# geneva-interface.net
KiCad netlist of a schematic drawn in Altium Designer
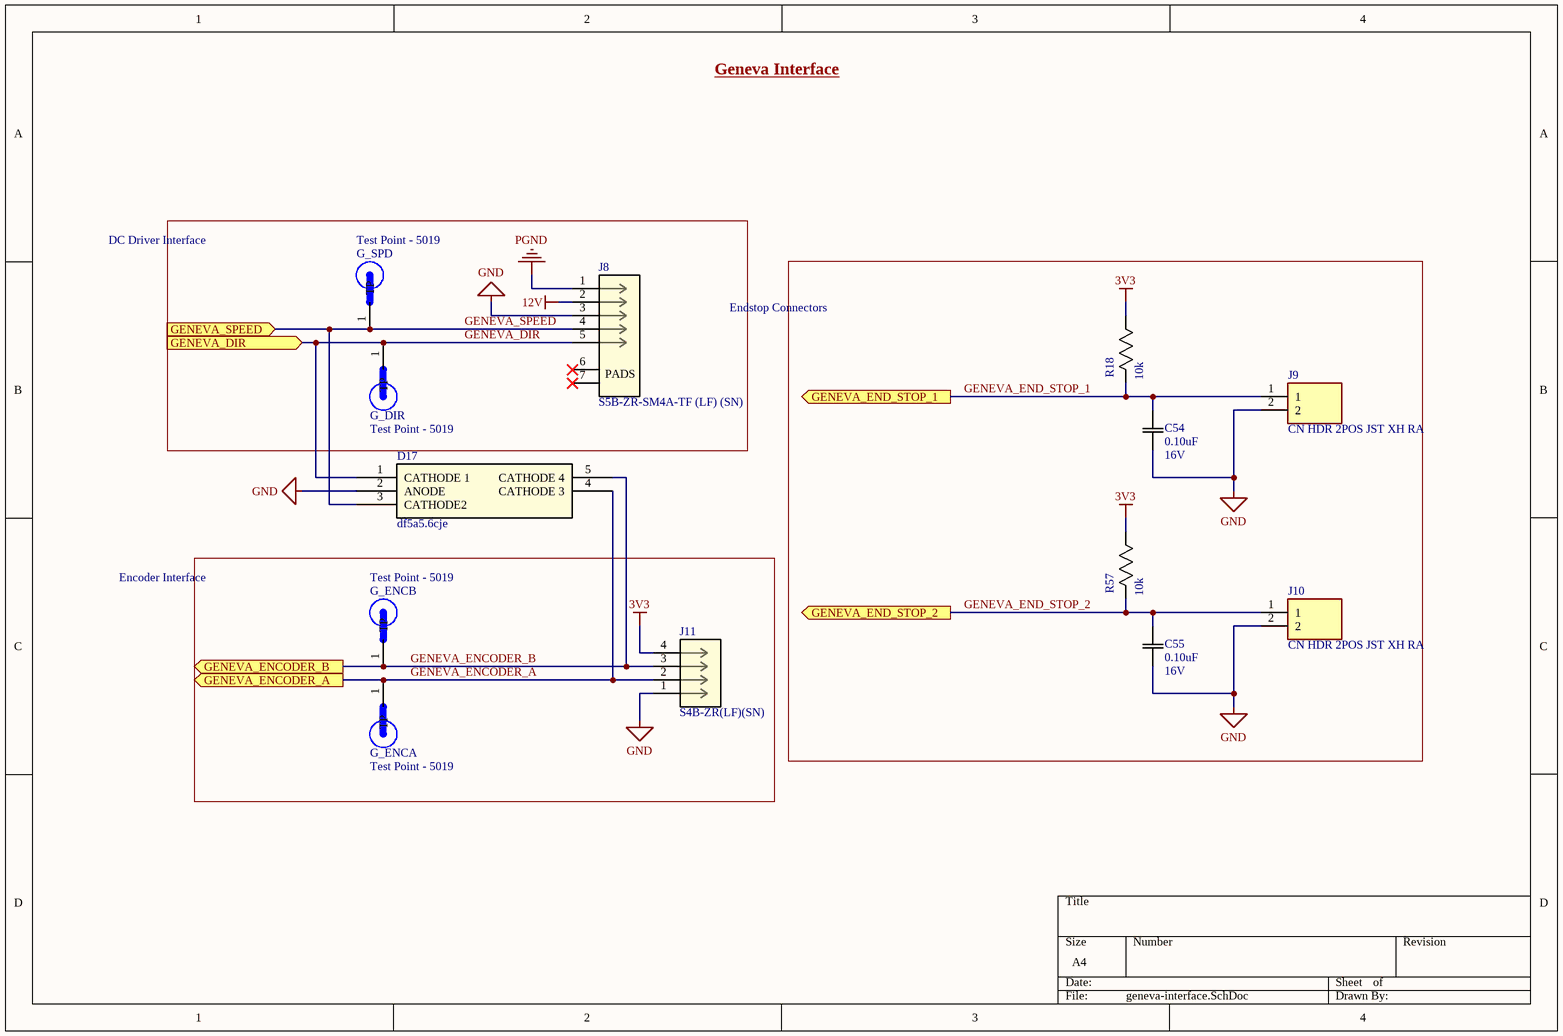
[diagram p0: geneva-interface.SchDoc]

(export (version "E")
  (design (tool "Eeschema 10.0.6"))
  (components
    (comp (ref "C54")
      (value "0.10uF")
      (footprint "0603")
      (description "CAP CER 0.10UF 16V X5R 0603")
      (fields
        (field (name "TOLERANCE") "10%")
        (field (name "RATING") "16V")
        (field (name "PART NUMBER") "CAP 0.10uF 16V")
      )
      (libsource (lib "capacitor_library") (part "CAP 0.10uF 16V"))
    )
    (comp (ref "C55")
      (value "0.10uF")
      (footprint "0603")
      (description "CAP CER 0.10UF 16V X5R 0603")
      (fields
        (field (name "TOLERANCE") "10%")
        (field (name "RATING") "16V")
        (field (name "PART NUMBER") "CAP 0.10uF 16V")
      )
      (libsource (lib "capacitor_library") (part "CAP 0.10uF 16V"))
    )
    (comp (ref "D17")
      (value "df5a5.6cje")
      (footprint "ESV_TOS-L")
      (description "- Clamp - Ipp Tvs Diode Surface Mount ESV 4 Channel")
      (fields
        (field (name "MANUFACTURER_PART_NUMBER") "df5a5.6cje(te85l")
        (field (name "PART NUMBER") "DIODE TVS 3.5 VWM 4 Channel")
        (field (name "COPYRIGHT") "Copyright (C) 2021 Ultra Librarian. All rights reserved.")
      )
      (libsource (lib "Diode_Library") (part "DIODE TVS 3.5 VWM 4 Channel"))
    )
    (comp (ref "G_DIR")
      (value "Test Point - 5019")
      (footprint "TP380X203")
      (description "PC Test Point, Miniature Phosphor Bronze, Silver Plating Surface Mount Mounting Type")
      (fields (field (name "MP") "5019") (field (name "MF") "Keystone Electronics"))
      (libsource (lib "IC_Library") (part "Test Point - 5019"))
    )
    (comp (ref "G_ENCA")
      (value "Test Point - 5019")
      (footprint "TP380X203")
      (description "PC Test Point, Miniature Phosphor Bronze, Silver Plating Surface Mount Mounting Type")
      (fields (field (name "MP") "5019") (field (name "MF") "Keystone Electronics"))
      (libsource (lib "IC_Library") (part "Test Point - 5019"))
    )
    (comp (ref "G_ENCB")
      (value "Test Point - 5019")
      (footprint "TP380X203")
      (description "PC Test Point, Miniature Phosphor Bronze, Silver Plating Surface Mount Mounting Type")
      (fields (field (name "MP") "5019") (field (name "MF") "Keystone Electronics"))
      (libsource (lib "IC_Library") (part "Test Point - 5019"))
    )
    (comp (ref "G_SPD")
      (value "Test Point - 5019")
      (footprint "TP380X203")
      (description "PC Test Point, Miniature Phosphor Bronze, Silver Plating Surface Mount Mounting Type")
      (fields (field (name "MP") "5019") (field (name "MF") "Keystone Electronics"))
      (libsource (lib "IC_Library") (part "Test Point - 5019"))
    )
    (comp (ref "J8")
      (value "S5B-ZR-SM4A-TF (LF) (SN)")
      (footprint "JST_S5B-ZR-SM4A-TF")
      (description "Connector Header Surface Mount, Right Angle 5 position 0.059\" (1.50mm)")
      (fields (field (name "PART NUMBER") "CN 5POS JST ZR RA"))
      (libsource (lib "Connector_Library") (part "CN 5POS JST ZR RA"))
    )
    (comp (ref "J9")
      (value "CN HDR 2POS JST XH RA")
      (footprint "JST_S2B-XH-A(LF)(SN)")
      (description "Connector Header Through Hole 2 position right angle 0.098 _2.50mm_\r\nJST XH")
      (fields (field (name "MP") "B2B-XH-A_LF__SN_") (field (name "MF") "JST Sales"))
      (libsource (lib "Connector_Library") (part "CN HDR 2POS JST XH RA"))
    )
    (comp (ref "J10")
      (value "CN HDR 2POS JST XH RA")
      (footprint "JST_S2B-XH-A(LF)(SN)")
      (description "Connector Header Through Hole 2 position right angle 0.098 _2.50mm_\r\nJST XH")
      (fields (field (name "MP") "B2B-XH-A_LF__SN_") (field (name "MF") "JST Sales"))
      (libsource (lib "Connector_Library") (part "CN HDR 2POS JST XH RA"))
    )
    (comp (ref "J11")
      (value "S4B-ZR(LF)(SN)")
      (footprint "CN S4B-ZR(LF)(SN)_JST")
      (description "Connector Header Through Hole, Right Angle 4 position 0.059\" (1.50mm)")
      (fields
        (field (name "PART NUMBER") "CN HDR 4POS JST ZR")
        (field (name "COPYRIGHT") "Copyright (C) 2021 Ultra Librarian. All rights reserved.")
      )
      (libsource (lib "Connector_Library") (part "CN HDR 4POS JST ZR"))
    )
    (comp (ref "R18")
      (value "10k")
      (footprint "0603")
      (description "RES SMD 10K OHM 5% 1/8W 0603")
      (fields (field (name "TOLERANCE") "5%") (field (name "PART NUMBER") "RES 10k 1/8W - 5%"))
      (libsource (lib "Resistor_Library") (part "RES 10k 1/8W 5%"))
    )
    (comp (ref "R57")
      (value "10k")
      (footprint "0603")
      (description "RES SMD 10K OHM 5% 1/8W 0603")
      (fields (field (name "TOLERANCE") "5%") (field (name "PART NUMBER") "RES 10k 1/8W - 5%"))
      (libsource (lib "Resistor_Library") (part "RES 10k 1/8W 5%"))
    )
  )
  (nets
    (net (code "1") (name "/GENEVA_DIR") (class "Default")
      (node (ref "D17") (pin "1") (pinfunction "CATHODE_1_1") (pintype "passive"))
      (node (ref "G_DIR") (pin "1") (pinfunction "TP_1") (pintype "passive"))
      (node (ref "J8") (pin "5") (pinfunction "5_5") (pintype "passive"))
    )
    (net (code "2") (name "/GENEVA_ENCODER_A") (class "Default")
      (node (ref "D17") (pin "4") (pinfunction "CATHODE_3_4") (pintype "passive"))
      (node (ref "G_ENCA") (pin "1") (pinfunction "TP_1") (pintype "passive"))
      (node (ref "J11") (pin "2") (pinfunction "2_2") (pintype "passive"))
    )
    (net (code "3") (name "/GENEVA_ENCODER_B") (class "Default")
      (node (ref "D17") (pin "5") (pinfunction "CATHODE_4_5") (pintype "passive"))
      (node (ref "G_ENCB") (pin "1") (pinfunction "TP_1") (pintype "passive"))
      (node (ref "J11") (pin "3") (pinfunction "3_3") (pintype "passive"))
    )
    (net (code "4") (name "/GENEVA_END_STOP_1") (class "Default")
      (node (ref "C54") (pin "1") (pinfunction "C1_1") (pintype "passive"))
      (node (ref "J9") (pin "1") (pinfunction "1_1") (pintype "passive"))
      (node (ref "R18") (pin "2") (pinfunction "R2_2") (pintype "passive"))
    )
    (net (code "5") (name "/GENEVA_END_STOP_2") (class "Default")
      (node (ref "C55") (pin "1") (pinfunction "C1_1") (pintype "passive"))
      (node (ref "J10") (pin "1") (pinfunction "1_1") (pintype "passive"))
      (node (ref "R57") (pin "2") (pinfunction "R2_2") (pintype "passive"))
    )
    (net (code "6") (name "/GENEVA_SPEED") (class "Default")
      (node (ref "D17") (pin "3") (pinfunction "CATHODE2_3") (pintype "passive"))
      (node (ref "G_SPD") (pin "1") (pinfunction "TP_1") (pintype "passive"))
      (node (ref "J8") (pin "4") (pinfunction "4_4") (pintype "passive"))
    )
    (net (code "7") (name "3V3") (class "Default")
      (node (ref "J11") (pin "4") (pinfunction "4_4") (pintype "passive"))
      (node (ref "R18") (pin "1") (pinfunction "R1_1") (pintype "passive"))
      (node (ref "R57") (pin "1") (pinfunction "R1_1") (pintype "passive"))
    )
    (net (code "8") (name "12V") (class "Default")
      (node (ref "J8") (pin "2") (pinfunction "2_2") (pintype "passive"))
    )
    (net (code "9") (name "GND") (class "Default")
      (node (ref "C54") (pin "2") (pinfunction "C2_2") (pintype "passive"))
      (node (ref "C55") (pin "2") (pinfunction "C2_2") (pintype "passive"))
      (node (ref "D17") (pin "2") (pinfunction "ANODE_2") (pintype "passive"))
      (node (ref "J10") (pin "2") (pinfunction "2_2") (pintype "passive"))
      (node (ref "J11") (pin "1") (pinfunction "1_1") (pintype "passive"))
      (node (ref "J8") (pin "3") (pinfunction "3_3") (pintype "passive"))
      (node (ref "J9") (pin "2") (pinfunction "2_2") (pintype "passive"))
    )
    (net (code "10") (name "PGND") (class "Default")
      (node (ref "J8") (pin "1") (pinfunction "1_1") (pintype "passive"))
    )
    (net (code "11") (name "unconnected-(J8-Pad6)") (class "Default")
      (node (ref "J8") (pin "6") (pinfunction "6_6") (pintype "passive+no_connect"))
    )
    (net (code "12") (name "unconnected-(J8-Pad7)") (class "Default")
      (node (ref "J8") (pin "7") (pinfunction "7_7") (pintype "passive+no_connect"))
    )
  )
)
